# board.net
KiCad netlist of a schematic drawn in EAGLE
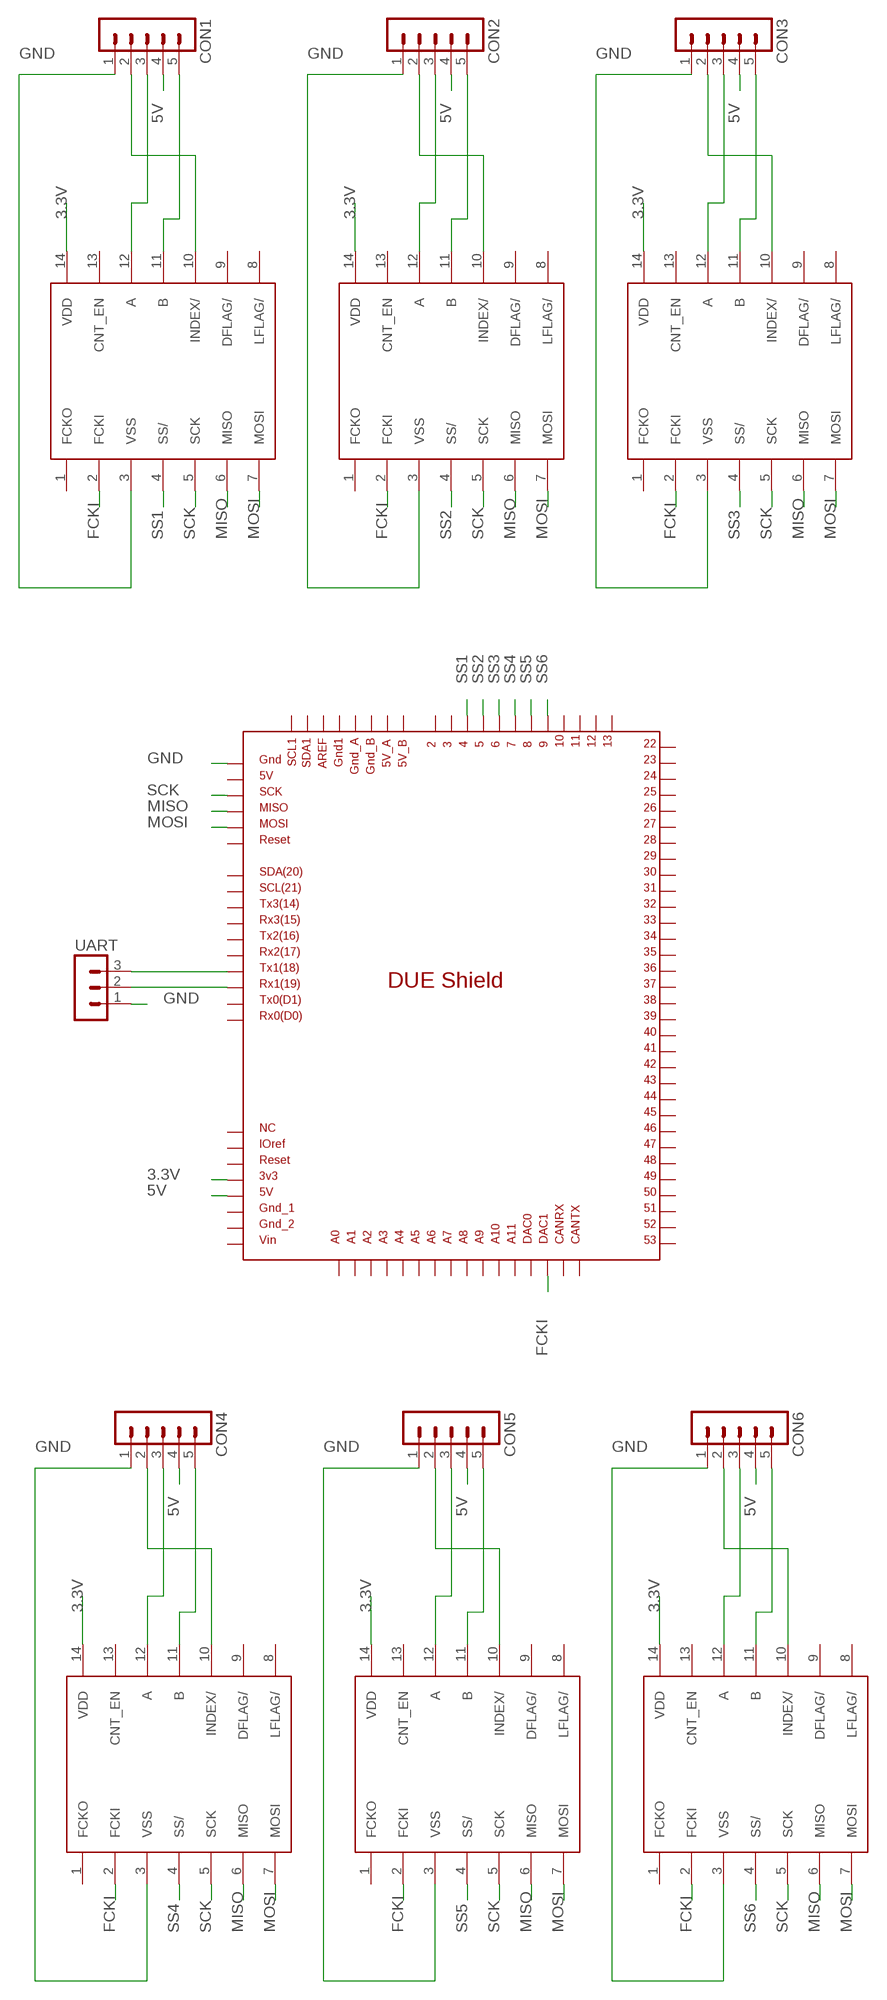
[diagram p0: schematic, sheet 1]

(export (version "E")
  (design (tool "Eeschema 10.0.6"))
  (components
    (comp (ref "CON1")
      (value "MA05-1")
      (footprint "eagle-import:MA05-1")
      (libsource (lib "eagle-import") (part "MA05-1"))
    )
    (comp (ref "CON2")
      (value "MA05-1")
      (footprint "eagle-import:MA05-1")
      (libsource (lib "eagle-import") (part "MA05-1"))
    )
    (comp (ref "CON3")
      (value "MA05-1")
      (footprint "eagle-import:MA05-1")
      (libsource (lib "eagle-import") (part "MA05-1"))
    )
    (comp (ref "CON4")
      (value "MA05-1(BOTTOM)")
      (footprint "eagle-import:MA05-1(BOTTOM)")
      (libsource (lib "eagle-import") (part "MA05-1(BOTTOM)"))
    )
    (comp (ref "CON5")
      (value "MA05-1(BOTTOM)")
      (footprint "eagle-import:MA05-1(BOTTOM)")
      (libsource (lib "eagle-import") (part "MA05-1(BOTTOM)"))
    )
    (comp (ref "CON6")
      (value "MA05-1(BOTTOM)")
      (footprint "eagle-import:MA05-1(BOTTOM)")
      (libsource (lib "eagle-import") (part "MA05-1(BOTTOM)"))
    )
    (comp (ref "IC1")
      (value "LFLS7366R")
      (footprint "eagle-import:SO14")
      (libsource (lib "eagle-import") (part "LFLS7366R"))
    )
    (comp (ref "IC2")
      (value "LFLS7366R")
      (footprint "eagle-import:SO14")
      (libsource (lib "eagle-import") (part "LFLS7366R"))
    )
    (comp (ref "IC3")
      (value "LFLS7366R")
      (footprint "eagle-import:SO14")
      (libsource (lib "eagle-import") (part "LFLS7366R"))
    )
    (comp (ref "IC4")
      (value "LFLS7366R")
      (footprint "eagle-import:SO14")
      (libsource (lib "eagle-import") (part "LFLS7366R"))
    )
    (comp (ref "IC5")
      (value "LFLS7366R")
      (footprint "eagle-import:SO14")
      (libsource (lib "eagle-import") (part "LFLS7366R"))
    )
    (comp (ref "IC6")
      (value "LFLS7366R")
      (footprint "eagle-import:SO14")
      (libsource (lib "eagle-import") (part "LFLS7366R"))
    )
    (comp (ref "U$1")
      (value "DUE(ENCODER)")
      (footprint "eagle-import:DUE(ENCODER)")
      (libsource (lib "eagle-import") (part "DUE(ENCODER)"))
    )
    (comp (ref "UART")
      (value "MA03-1")
      (footprint "eagle-import:MA03-1")
      (libsource (lib "eagle-import") (part "MA03-1"))
    )
  )
  (nets
    (net (code "1") (name "/3.3V") (class "Default")
      (node (ref "IC1") (pin "14") (pinfunction "VDD_14") (pintype "bidirectional"))
      (node (ref "IC2") (pin "14") (pinfunction "VDD_14") (pintype "bidirectional"))
      (node (ref "IC3") (pin "14") (pinfunction "VDD_14") (pintype "bidirectional"))
      (node (ref "IC4") (pin "14") (pinfunction "VDD_14") (pintype "bidirectional"))
      (node (ref "IC5") (pin "14") (pinfunction "VDD_14") (pintype "bidirectional"))
      (node (ref "IC6") (pin "14") (pinfunction "VDD_14") (pintype "bidirectional"))
      (node (ref "U$1") (pin "3V3") (pinfunction "3V3_3V3") (pintype "bidirectional"))
    )
    (net (code "2") (name "/5V") (class "Default")
      (node (ref "CON1") (pin "4") (pinfunction "4_4") (pintype "passive"))
      (node (ref "CON2") (pin "4") (pinfunction "4_4") (pintype "passive"))
      (node (ref "CON3") (pin "4") (pinfunction "4_4") (pintype "passive"))
      (node (ref "CON4") (pin "4") (pinfunction "4_4") (pintype "passive"))
      (node (ref "CON5") (pin "4") (pinfunction "4_4") (pintype "passive"))
      (node (ref "CON6") (pin "4") (pinfunction "4_4") (pintype "passive"))
      (node (ref "U$1") (pin "5V") (pinfunction "5V_5V") (pintype "bidirectional"))
    )
    (net (code "3") (name "/FCKI") (class "Default")
      (node (ref "IC1") (pin "2") (pinfunction "FCKI_2") (pintype "bidirectional"))
      (node (ref "IC2") (pin "2") (pinfunction "FCKI_2") (pintype "bidirectional"))
      (node (ref "IC3") (pin "2") (pinfunction "FCKI_2") (pintype "bidirectional"))
      (node (ref "IC4") (pin "2") (pinfunction "FCKI_2") (pintype "bidirectional"))
      (node (ref "IC5") (pin "2") (pinfunction "FCKI_2") (pintype "bidirectional"))
      (node (ref "IC6") (pin "2") (pinfunction "FCKI_2") (pintype "bidirectional"))
      (node (ref "U$1") (pin "DAC1") (pinfunction "DAC1_DAC1") (pintype "bidirectional"))
    )
    (net (code "4") (name "/GND") (class "Default")
      (node (ref "CON1") (pin "1") (pinfunction "1_1") (pintype "passive"))
      (node (ref "CON2") (pin "1") (pinfunction "1_1") (pintype "passive"))
      (node (ref "CON3") (pin "1") (pinfunction "1_1") (pintype "passive"))
      (node (ref "CON4") (pin "1") (pinfunction "1_1") (pintype "passive"))
      (node (ref "CON5") (pin "1") (pinfunction "1_1") (pintype "passive"))
      (node (ref "CON6") (pin "1") (pinfunction "1_1") (pintype "passive"))
      (node (ref "IC1") (pin "3") (pinfunction "VSS_3") (pintype "bidirectional"))
      (node (ref "IC2") (pin "3") (pinfunction "VSS_3") (pintype "bidirectional"))
      (node (ref "IC3") (pin "3") (pinfunction "VSS_3") (pintype "bidirectional"))
      (node (ref "IC4") (pin "3") (pinfunction "VSS_3") (pintype "bidirectional"))
      (node (ref "IC5") (pin "3") (pinfunction "VSS_3") (pintype "bidirectional"))
      (node (ref "IC6") (pin "3") (pinfunction "VSS_3") (pintype "bidirectional"))
      (node (ref "U$1") (pin "5V_ICSP") (pinfunction "5V_ICSP_5V_ICSP") (pintype "bidirectional"))
      (node (ref "UART") (pin "1") (pinfunction "1_1") (pintype "passive"))
    )
    (net (code "5") (name "/MISO") (class "Default")
      (node (ref "IC1") (pin "6") (pinfunction "MISO_6") (pintype "bidirectional"))
      (node (ref "IC2") (pin "6") (pinfunction "MISO_6") (pintype "bidirectional"))
      (node (ref "IC3") (pin "6") (pinfunction "MISO_6") (pintype "bidirectional"))
      (node (ref "IC4") (pin "6") (pinfunction "MISO_6") (pintype "bidirectional"))
      (node (ref "IC5") (pin "6") (pinfunction "MISO_6") (pintype "bidirectional"))
      (node (ref "IC6") (pin "6") (pinfunction "MISO_6") (pintype "bidirectional"))
      (node (ref "U$1") (pin "MISO_ICSP") (pinfunction "MISO_ICSP_MISO_ICSP") (pintype "bidirectional"))
    )
    (net (code "6") (name "/MOSI") (class "Default")
      (node (ref "IC1") (pin "7") (pinfunction "MOSI_7") (pintype "bidirectional"))
      (node (ref "IC2") (pin "7") (pinfunction "MOSI_7") (pintype "bidirectional"))
      (node (ref "IC3") (pin "7") (pinfunction "MOSI_7") (pintype "bidirectional"))
      (node (ref "IC4") (pin "7") (pinfunction "MOSI_7") (pintype "bidirectional"))
      (node (ref "IC5") (pin "7") (pinfunction "MOSI_7") (pintype "bidirectional"))
      (node (ref "IC6") (pin "7") (pinfunction "MOSI_7") (pintype "bidirectional"))
      (node (ref "U$1") (pin "MOSI_ICSP") (pinfunction "MOSI_ICSP_MOSI_ICSP") (pintype "bidirectional"))
    )
    (net (code "7") (name "/SCK") (class "Default")
      (node (ref "IC1") (pin "5") (pinfunction "SCK_5") (pintype "bidirectional"))
      (node (ref "IC2") (pin "5") (pinfunction "SCK_5") (pintype "bidirectional"))
      (node (ref "IC3") (pin "5") (pinfunction "SCK_5") (pintype "bidirectional"))
      (node (ref "IC4") (pin "5") (pinfunction "SCK_5") (pintype "bidirectional"))
      (node (ref "IC5") (pin "5") (pinfunction "SCK_5") (pintype "bidirectional"))
      (node (ref "IC6") (pin "5") (pinfunction "SCK_5") (pintype "bidirectional"))
      (node (ref "U$1") (pin "SCK_ICSP") (pinfunction "SCK_ICSP_SCK_ICSP") (pintype "bidirectional"))
    )
    (net (code "8") (name "/SS1") (class "Default")
      (node (ref "IC1") (pin "4") (pinfunction "SS/_4") (pintype "bidirectional"))
      (node (ref "U$1") (pin "4") (pinfunction "4_4") (pintype "bidirectional"))
    )
    (net (code "9") (name "/SS2") (class "Default")
      (node (ref "IC2") (pin "4") (pinfunction "SS/_4") (pintype "bidirectional"))
      (node (ref "U$1") (pin "5") (pinfunction "5_5") (pintype "bidirectional"))
    )
    (net (code "10") (name "/SS3") (class "Default")
      (node (ref "IC3") (pin "4") (pinfunction "SS/_4") (pintype "bidirectional"))
      (node (ref "U$1") (pin "6") (pinfunction "6_6") (pintype "bidirectional"))
    )
    (net (code "11") (name "/SS4") (class "Default")
      (node (ref "IC4") (pin "4") (pinfunction "SS/_4") (pintype "bidirectional"))
      (node (ref "U$1") (pin "7") (pinfunction "7_7") (pintype "bidirectional"))
    )
    (net (code "12") (name "/SS5") (class "Default")
      (node (ref "IC5") (pin "4") (pinfunction "SS/_4") (pintype "bidirectional"))
      (node (ref "U$1") (pin "8") (pinfunction "8_8") (pintype "bidirectional"))
    )
    (net (code "13") (name "/SS6") (class "Default")
      (node (ref "IC6") (pin "4") (pinfunction "SS/_4") (pintype "bidirectional"))
      (node (ref "U$1") (pin "9") (pinfunction "9_9") (pintype "bidirectional"))
    )
    (net (code "14") (name "Net-(IC1-A)") (class "Default")
      (node (ref "CON1") (pin "3") (pinfunction "3_3") (pintype "passive"))
      (node (ref "IC1") (pin "12") (pinfunction "A_12") (pintype "bidirectional"))
    )
    (net (code "15") (name "Net-(IC1-B)") (class "Default")
      (node (ref "CON1") (pin "5") (pinfunction "5_5") (pintype "passive"))
      (node (ref "IC1") (pin "11") (pinfunction "B_11") (pintype "bidirectional"))
    )
    (net (code "16") (name "Net-(IC1-INDEX{slash})") (class "Default")
      (node (ref "CON1") (pin "2") (pinfunction "2_2") (pintype "passive"))
      (node (ref "IC1") (pin "10") (pinfunction "INDEX/_10") (pintype "bidirectional"))
    )
    (net (code "17") (name "Net-(IC2-A)") (class "Default")
      (node (ref "CON2") (pin "3") (pinfunction "3_3") (pintype "passive"))
      (node (ref "IC2") (pin "12") (pinfunction "A_12") (pintype "bidirectional"))
    )
    (net (code "18") (name "Net-(IC2-B)") (class "Default")
      (node (ref "CON2") (pin "5") (pinfunction "5_5") (pintype "passive"))
      (node (ref "IC2") (pin "11") (pinfunction "B_11") (pintype "bidirectional"))
    )
    (net (code "19") (name "Net-(IC2-INDEX{slash})") (class "Default")
      (node (ref "CON2") (pin "2") (pinfunction "2_2") (pintype "passive"))
      (node (ref "IC2") (pin "10") (pinfunction "INDEX/_10") (pintype "bidirectional"))
    )
    (net (code "20") (name "Net-(IC3-A)") (class "Default")
      (node (ref "CON3") (pin "3") (pinfunction "3_3") (pintype "passive"))
      (node (ref "IC3") (pin "12") (pinfunction "A_12") (pintype "bidirectional"))
    )
    (net (code "21") (name "Net-(IC3-B)") (class "Default")
      (node (ref "CON3") (pin "5") (pinfunction "5_5") (pintype "passive"))
      (node (ref "IC3") (pin "11") (pinfunction "B_11") (pintype "bidirectional"))
    )
    (net (code "22") (name "Net-(IC3-INDEX{slash})") (class "Default")
      (node (ref "CON3") (pin "2") (pinfunction "2_2") (pintype "passive"))
      (node (ref "IC3") (pin "10") (pinfunction "INDEX/_10") (pintype "bidirectional"))
    )
    (net (code "23") (name "Net-(IC4-A)") (class "Default")
      (node (ref "CON4") (pin "3") (pinfunction "3_3") (pintype "passive"))
      (node (ref "IC4") (pin "12") (pinfunction "A_12") (pintype "bidirectional"))
    )
    (net (code "24") (name "Net-(IC4-B)") (class "Default")
      (node (ref "CON4") (pin "5") (pinfunction "5_5") (pintype "passive"))
      (node (ref "IC4") (pin "11") (pinfunction "B_11") (pintype "bidirectional"))
    )
    (net (code "25") (name "Net-(IC4-INDEX{slash})") (class "Default")
      (node (ref "CON4") (pin "2") (pinfunction "2_2") (pintype "passive"))
      (node (ref "IC4") (pin "10") (pinfunction "INDEX/_10") (pintype "bidirectional"))
    )
    (net (code "26") (name "Net-(IC5-A)") (class "Default")
      (node (ref "CON5") (pin "3") (pinfunction "3_3") (pintype "passive"))
      (node (ref "IC5") (pin "12") (pinfunction "A_12") (pintype "bidirectional"))
    )
    (net (code "27") (name "Net-(IC5-B)") (class "Default")
      (node (ref "CON5") (pin "5") (pinfunction "5_5") (pintype "passive"))
      (node (ref "IC5") (pin "11") (pinfunction "B_11") (pintype "bidirectional"))
    )
    (net (code "28") (name "Net-(IC5-INDEX{slash})") (class "Default")
      (node (ref "CON5") (pin "2") (pinfunction "2_2") (pintype "passive"))
      (node (ref "IC5") (pin "10") (pinfunction "INDEX/_10") (pintype "bidirectional"))
    )
    (net (code "29") (name "Net-(IC6-A)") (class "Default")
      (node (ref "CON6") (pin "3") (pinfunction "3_3") (pintype "passive"))
      (node (ref "IC6") (pin "12") (pinfunction "A_12") (pintype "bidirectional"))
    )
    (net (code "30") (name "Net-(IC6-B)") (class "Default")
      (node (ref "CON6") (pin "5") (pinfunction "5_5") (pintype "passive"))
      (node (ref "IC6") (pin "11") (pinfunction "B_11") (pintype "bidirectional"))
    )
    (net (code "31") (name "Net-(IC6-INDEX{slash})") (class "Default")
      (node (ref "CON6") (pin "2") (pinfunction "2_2") (pintype "passive"))
      (node (ref "IC6") (pin "10") (pinfunction "INDEX/_10") (pintype "bidirectional"))
    )
    (net (code "32") (name "Net-(U$1-PadRX1)") (class "Default")
      (node (ref "U$1") (pin "RX1") (pinfunction "RX1_RX1") (pintype "bidirectional"))
      (node (ref "UART") (pin "2") (pinfunction "2_2") (pintype "passive"))
    )
    (net (code "33") (name "Net-(U$1-PadTX1)") (class "Default")
      (node (ref "U$1") (pin "TX1") (pinfunction "TX1_TX1") (pintype "bidirectional"))
      (node (ref "UART") (pin "3") (pinfunction "3_3") (pintype "passive"))
    )
    (net (code "34") (name "unconnected-(IC1-CNT_EN-Pad13)") (class "Default")
      (node (ref "IC1") (pin "13") (pinfunction "CNT_EN_13") (pintype "bidirectional"))
    )
    (net (code "35") (name "unconnected-(IC1-DFLAG{slash}-Pad9)") (class "Default")
      (node (ref "IC1") (pin "9") (pinfunction "DFLAG/_9") (pintype "bidirectional"))
    )
    (net (code "36") (name "unconnected-(IC1-FCKO-Pad1)") (class "Default")
      (node (ref "IC1") (pin "1") (pinfunction "FCKO_1") (pintype "bidirectional"))
    )
    (net (code "37") (name "unconnected-(IC1-LFLAG{slash}-Pad8)") (class "Default")
      (node (ref "IC1") (pin "8") (pinfunction "LFLAG/_8") (pintype "bidirectional"))
    )
    (net (code "38") (name "unconnected-(IC2-CNT_EN-Pad13)") (class "Default")
      (node (ref "IC2") (pin "13") (pinfunction "CNT_EN_13") (pintype "bidirectional"))
    )
    (net (code "39") (name "unconnected-(IC2-DFLAG{slash}-Pad9)") (class "Default")
      (node (ref "IC2") (pin "9") (pinfunction "DFLAG/_9") (pintype "bidirectional"))
    )
    (net (code "40") (name "unconnected-(IC2-FCKO-Pad1)") (class "Default")
      (node (ref "IC2") (pin "1") (pinfunction "FCKO_1") (pintype "bidirectional"))
    )
    (net (code "41") (name "unconnected-(IC2-LFLAG{slash}-Pad8)") (class "Default")
      (node (ref "IC2") (pin "8") (pinfunction "LFLAG/_8") (pintype "bidirectional"))
    )
    (net (code "42") (name "unconnected-(IC3-CNT_EN-Pad13)") (class "Default")
      (node (ref "IC3") (pin "13") (pinfunction "CNT_EN_13") (pintype "bidirectional"))
    )
    (net (code "43") (name "unconnected-(IC3-DFLAG{slash}-Pad9)") (class "Default")
      (node (ref "IC3") (pin "9") (pinfunction "DFLAG/_9") (pintype "bidirectional"))
    )
    (net (code "44") (name "unconnected-(IC3-FCKO-Pad1)") (class "Default")
      (node (ref "IC3") (pin "1") (pinfunction "FCKO_1") (pintype "bidirectional"))
    )
    (net (code "45") (name "unconnected-(IC3-LFLAG{slash}-Pad8)") (class "Default")
      (node (ref "IC3") (pin "8") (pinfunction "LFLAG/_8") (pintype "bidirectional"))
    )
    (net (code "46") (name "unconnected-(IC4-CNT_EN-Pad13)") (class "Default")
      (node (ref "IC4") (pin "13") (pinfunction "CNT_EN_13") (pintype "bidirectional"))
    )
    (net (code "47") (name "unconnected-(IC4-DFLAG{slash}-Pad9)") (class "Default")
      (node (ref "IC4") (pin "9") (pinfunction "DFLAG/_9") (pintype "bidirectional"))
    )
    (net (code "48") (name "unconnected-(IC4-FCKO-Pad1)") (class "Default")
      (node (ref "IC4") (pin "1") (pinfunction "FCKO_1") (pintype "bidirectional"))
    )
    (net (code "49") (name "unconnected-(IC4-LFLAG{slash}-Pad8)") (class "Default")
      (node (ref "IC4") (pin "8") (pinfunction "LFLAG/_8") (pintype "bidirectional"))
    )
    (net (code "50") (name "unconnected-(IC5-CNT_EN-Pad13)") (class "Default")
      (node (ref "IC5") (pin "13") (pinfunction "CNT_EN_13") (pintype "bidirectional"))
    )
    (net (code "51") (name "unconnected-(IC5-DFLAG{slash}-Pad9)") (class "Default")
      (node (ref "IC5") (pin "9") (pinfunction "DFLAG/_9") (pintype "bidirectional"))
    )
    (net (code "52") (name "unconnected-(IC5-FCKO-Pad1)") (class "Default")
      (node (ref "IC5") (pin "1") (pinfunction "FCKO_1") (pintype "bidirectional"))
    )
    (net (code "53") (name "unconnected-(IC5-LFLAG{slash}-Pad8)") (class "Default")
      (node (ref "IC5") (pin "8") (pinfunction "LFLAG/_8") (pintype "bidirectional"))
    )
    (net (code "54") (name "unconnected-(IC6-CNT_EN-Pad13)") (class "Default")
      (node (ref "IC6") (pin "13") (pinfunction "CNT_EN_13") (pintype "bidirectional"))
    )
    (net (code "55") (name "unconnected-(IC6-DFLAG{slash}-Pad9)") (class "Default")
      (node (ref "IC6") (pin "9") (pinfunction "DFLAG/_9") (pintype "bidirectional"))
    )
    (net (code "56") (name "unconnected-(IC6-FCKO-Pad1)") (class "Default")
      (node (ref "IC6") (pin "1") (pinfunction "FCKO_1") (pintype "bidirectional"))
    )
    (net (code "57") (name "unconnected-(IC6-LFLAG{slash}-Pad8)") (class "Default")
      (node (ref "IC6") (pin "8") (pinfunction "LFLAG/_8") (pintype "bidirectional"))
    )
    (net (code "58") (name "unconnected-(U$1-Pad2)") (class "Default")
      (node (ref "U$1") (pin "2") (pinfunction "2_2") (pintype "bidirectional"))
    )
    (net (code "59") (name "unconnected-(U$1-Pad3)") (class "Default")
      (node (ref "U$1") (pin "3") (pinfunction "3_3") (pintype "bidirectional"))
    )
    (net (code "60") (name "unconnected-(U$1-Pad5V_A)") (class "Default")
      (node (ref "U$1") (pin "5V_A") (pinfunction "5V_A_5V_A") (pintype "bidirectional"))
    )
    (net (code "61") (name "unconnected-(U$1-Pad5V_B)") (class "Default")
      (node (ref "U$1") (pin "5V_B") (pinfunction "5V_B_5V_B") (pintype "bidirectional"))
    )
    (net (code "62") (name "unconnected-(U$1-Pad10)") (class "Default")
      (node (ref "U$1") (pin "10") (pinfunction "10_10") (pintype "bidirectional"))
    )
    (net (code "63") (name "unconnected-(U$1-Pad11)") (class "Default")
      (node (ref "U$1") (pin "11") (pinfunction "11_11") (pintype "bidirectional"))
    )
    (net (code "64") (name "unconnected-(U$1-Pad12)") (class "Default")
      (node (ref "U$1") (pin "12") (pinfunction "12_12") (pintype "bidirectional"))
    )
    (net (code "65") (name "unconnected-(U$1-Pad13)") (class "Default")
      (node (ref "U$1") (pin "13") (pinfunction "13_13") (pintype "bidirectional"))
    )
    (net (code "66") (name "unconnected-(U$1-Pad22)") (class "Default")
      (node (ref "U$1") (pin "22") (pinfunction "22_22") (pintype "bidirectional"))
    )
    (net (code "67") (name "unconnected-(U$1-Pad23)") (class "Default")
      (node (ref "U$1") (pin "23") (pinfunction "23_23") (pintype "bidirectional"))
    )
    (net (code "68") (name "unconnected-(U$1-Pad24)") (class "Default")
      (node (ref "U$1") (pin "24") (pinfunction "24_24") (pintype "bidirectional"))
    )
    (net (code "69") (name "unconnected-(U$1-Pad25)") (class "Default")
      (node (ref "U$1") (pin "25") (pinfunction "25_25") (pintype "bidirectional"))
    )
    (net (code "70") (name "unconnected-(U$1-Pad26)") (class "Default")
      (node (ref "U$1") (pin "26") (pinfunction "26_26") (pintype "bidirectional"))
    )
    (net (code "71") (name "unconnected-(U$1-Pad27)") (class "Default")
      (node (ref "U$1") (pin "27") (pinfunction "27_27") (pintype "bidirectional"))
    )
    (net (code "72") (name "unconnected-(U$1-Pad28)") (class "Default")
      (node (ref "U$1") (pin "28") (pinfunction "28_28") (pintype "bidirectional"))
    )
    (net (code "73") (name "unconnected-(U$1-Pad29)") (class "Default")
      (node (ref "U$1") (pin "29") (pinfunction "29_29") (pintype "bidirectional"))
    )
    (net (code "74") (name "unconnected-(U$1-Pad30)") (class "Default")
      (node (ref "U$1") (pin "30") (pinfunction "30_30") (pintype "bidirectional"))
    )
    (net (code "75") (name "unconnected-(U$1-Pad31)") (class "Default")
      (node (ref "U$1") (pin "31") (pinfunction "31_31") (pintype "bidirectional"))
    )
    (net (code "76") (name "unconnected-(U$1-Pad32)") (class "Default")
      (node (ref "U$1") (pin "32") (pinfunction "32_32") (pintype "bidirectional"))
    )
    (net (code "77") (name "unconnected-(U$1-Pad33)") (class "Default")
      (node (ref "U$1") (pin "33") (pinfunction "33_33") (pintype "bidirectional"))
    )
    (net (code "78") (name "unconnected-(U$1-Pad34)") (class "Default")
      (node (ref "U$1") (pin "34") (pinfunction "34_34") (pintype "bidirectional"))
    )
    (net (code "79") (name "unconnected-(U$1-Pad35)") (class "Default")
      (node (ref "U$1") (pin "35") (pinfunction "35_35") (pintype "bidirectional"))
    )
    (net (code "80") (name "unconnected-(U$1-Pad36)") (class "Default")
      (node (ref "U$1") (pin "36") (pinfunction "36_36") (pintype "bidirectional"))
    )
    (net (code "81") (name "unconnected-(U$1-Pad37)") (class "Default")
      (node (ref "U$1") (pin "37") (pinfunction "37_37") (pintype "bidirectional"))
    )
    (net (code "82") (name "unconnected-(U$1-Pad38)") (class "Default")
      (node (ref "U$1") (pin "38") (pinfunction "38_38") (pintype "bidirectional"))
    )
    (net (code "83") (name "unconnected-(U$1-Pad39)") (class "Default")
      (node (ref "U$1") (pin "39") (pinfunction "39_39") (pintype "bidirectional"))
    )
    (net (code "84") (name "unconnected-(U$1-Pad40)") (class "Default")
      (node (ref "U$1") (pin "40") (pinfunction "40_40") (pintype "bidirectional"))
    )
    (net (code "85") (name "unconnected-(U$1-Pad41)") (class "Default")
      (node (ref "U$1") (pin "41") (pinfunction "41_41") (pintype "bidirectional"))
    )
    (net (code "86") (name "unconnected-(U$1-Pad42)") (class "Default")
      (node (ref "U$1") (pin "42") (pinfunction "42_42") (pintype "bidirectional"))
    )
    (net (code "87") (name "unconnected-(U$1-Pad43)") (class "Default")
      (node (ref "U$1") (pin "43") (pinfunction "43_43") (pintype "bidirectional"))
    )
    (net (code "88") (name "unconnected-(U$1-Pad44)") (class "Default")
      (node (ref "U$1") (pin "44") (pinfunction "44_44") (pintype "bidirectional"))
    )
    (net (code "89") (name "unconnected-(U$1-Pad45)") (class "Default")
      (node (ref "U$1") (pin "45") (pinfunction "45_45") (pintype "bidirectional"))
    )
    (net (code "90") (name "unconnected-(U$1-Pad46)") (class "Default")
      (node (ref "U$1") (pin "46") (pinfunction "46_46") (pintype "bidirectional"))
    )
    (net (code "91") (name "unconnected-(U$1-Pad47)") (class "Default")
      (node (ref "U$1") (pin "47") (pinfunction "47_47") (pintype "bidirectional"))
    )
    (net (code "92") (name "unconnected-(U$1-Pad48)") (class "Default")
      (node (ref "U$1") (pin "48") (pinfunction "48_48") (pintype "bidirectional"))
    )
    (net (code "93") (name "unconnected-(U$1-Pad49)") (class "Default")
      (node (ref "U$1") (pin "49") (pinfunction "49_49") (pintype "bidirectional"))
    )
    (net (code "94") (name "unconnected-(U$1-Pad50)") (class "Default")
      (node (ref "U$1") (pin "50") (pinfunction "50_50") (pintype "bidirectional"))
    )
    (net (code "95") (name "unconnected-(U$1-Pad51)") (class "Default")
      (node (ref "U$1") (pin "51") (pinfunction "51_51") (pintype "bidirectional"))
    )
    (net (code "96") (name "unconnected-(U$1-Pad52)") (class "Default")
      (node (ref "U$1") (pin "52") (pinfunction "52_52") (pintype "bidirectional"))
    )
    (net (code "97") (name "unconnected-(U$1-Pad53)") (class "Default")
      (node (ref "U$1") (pin "53") (pinfunction "53_53") (pintype "bidirectional"))
    )
    (net (code "98") (name "unconnected-(U$1-PadA0)") (class "Default")
      (node (ref "U$1") (pin "A0") (pinfunction "A0_A0") (pintype "bidirectional"))
    )
    (net (code "99") (name "unconnected-(U$1-PadA1)") (class "Default")
      (node (ref "U$1") (pin "A1") (pinfunction "A1_A1") (pintype "bidirectional"))
    )
    (net (code "100") (name "unconnected-(U$1-PadA2)") (class "Default")
      (node (ref "U$1") (pin "A2") (pinfunction "A2_A2") (pintype "bidirectional"))
    )
    (net (code "101") (name "unconnected-(U$1-PadA3)") (class "Default")
      (node (ref "U$1") (pin "A3") (pinfunction "A3_A3") (pintype "bidirectional"))
    )
    (net (code "102") (name "unconnected-(U$1-PadA4)") (class "Default")
      (node (ref "U$1") (pin "A4") (pinfunction "A4_A4") (pintype "bidirectional"))
    )
    (net (code "103") (name "unconnected-(U$1-PadA5)") (class "Default")
      (node (ref "U$1") (pin "A5") (pinfunction "A5_A5") (pintype "bidirectional"))
    )
    (net (code "104") (name "unconnected-(U$1-PadA6)") (class "Default")
      (node (ref "U$1") (pin "A6") (pinfunction "A6_A6") (pintype "bidirectional"))
    )
    (net (code "105") (name "unconnected-(U$1-PadA7)") (class "Default")
      (node (ref "U$1") (pin "A7") (pinfunction "A7_A7") (pintype "bidirectional"))
    )
    (net (code "106") (name "unconnected-(U$1-PadA8)") (class "Default")
      (node (ref "U$1") (pin "A8") (pinfunction "A8_A8") (pintype "bidirectional"))
    )
    (net (code "107") (name "unconnected-(U$1-PadA9)") (class "Default")
      (node (ref "U$1") (pin "A9") (pinfunction "A9_A9") (pintype "bidirectional"))
    )
    (net (code "108") (name "unconnected-(U$1-PadA10)") (class "Default")
      (node (ref "U$1") (pin "A10") (pinfunction "A10_A10") (pintype "bidirectional"))
    )
    (net (code "109") (name "unconnected-(U$1-PadA11)") (class "Default")
      (node (ref "U$1") (pin "A11") (pinfunction "A11_A11") (pintype "bidirectional"))
    )
    (net (code "110") (name "unconnected-(U$1-PadAREF)") (class "Default")
      (node (ref "U$1") (pin "AREF") (pinfunction "AREF_AREF") (pintype "bidirectional"))
    )
    (net (code "111") (name "unconnected-(U$1-PadCANRX)") (class "Default")
      (node (ref "U$1") (pin "CANRX") (pinfunction "CANRX_CANRX") (pintype "bidirectional"))
    )
    (net (code "112") (name "unconnected-(U$1-PadCANTX)") (class "Default")
      (node (ref "U$1") (pin "CANTX") (pinfunction "CANTX_CANTX") (pintype "bidirectional"))
    )
    (net (code "113") (name "unconnected-(U$1-PadDAC0)") (class "Default")
      (node (ref "U$1") (pin "DAC0") (pinfunction "DAC0_DAC0") (pintype "bidirectional"))
    )
    (net (code "114") (name "unconnected-(U$1-PadGND1)") (class "Default")
      (node (ref "U$1") (pin "GND1") (pinfunction "GND1_GND1") (pintype "bidirectional"))
    )
    (net (code "115") (name "unconnected-(U$1-PadGND_1)") (class "Default")
      (node (ref "U$1") (pin "GND_1") (pinfunction "GND_1_GND_1") (pintype "bidirectional"))
    )
    (net (code "116") (name "unconnected-(U$1-PadGND_2)") (class "Default")
      (node (ref "U$1") (pin "GND_2") (pinfunction "GND_2_GND_2") (pintype "bidirectional"))
    )
    (net (code "117") (name "unconnected-(U$1-PadGND_A)") (class "Default")
      (node (ref "U$1") (pin "GND_A") (pinfunction "GND_A_GND_A") (pintype "bidirectional"))
    )
    (net (code "118") (name "unconnected-(U$1-PadGND_B)") (class "Default")
      (node (ref "U$1") (pin "GND_B") (pinfunction "GND_B_GND_B") (pintype "bidirectional"))
    )
    (net (code "119") (name "unconnected-(U$1-PadGND_ICSP)") (class "Default")
      (node (ref "U$1") (pin "GND_ICSP") (pinfunction "GND_ICSP_GND_ICSP") (pintype "bidirectional"))
    )
    (net (code "120") (name "unconnected-(U$1-PadIOREF)") (class "Default")
      (node (ref "U$1") (pin "IOREF") (pinfunction "IOREF_IOREF") (pintype "bidirectional"))
    )
    (net (code "121") (name "unconnected-(U$1-PadNC)") (class "Default")
      (node (ref "U$1") (pin "NC") (pinfunction "NC_NC") (pintype "bidirectional"))
    )
    (net (code "122") (name "unconnected-(U$1-PadRESET)") (class "Default")
      (node (ref "U$1") (pin "RESET") (pinfunction "RESET_RESET") (pintype "bidirectional"))
    )
    (net (code "123") (name "unconnected-(U$1-PadRESET_ICSP)") (class "Default")
      (node (ref "U$1") (pin "RESET_ICSP") (pinfunction "RESET_ICSP_RESET_ICSP") (pintype "bidirectional"))
    )
    (net (code "124") (name "unconnected-(U$1-PadRX0)") (class "Default")
      (node (ref "U$1") (pin "RX0") (pinfunction "RX0_RX0") (pintype "bidirectional"))
    )
    (net (code "125") (name "unconnected-(U$1-PadRX2)") (class "Default")
      (node (ref "U$1") (pin "RX2") (pinfunction "RX2_RX2") (pintype "bidirectional"))
    )
    (net (code "126") (name "unconnected-(U$1-PadRX3)") (class "Default")
      (node (ref "U$1") (pin "RX3") (pinfunction "RX3_RX3") (pintype "bidirectional"))
    )
    (net (code "127") (name "unconnected-(U$1-PadSCL)") (class "Default")
      (node (ref "U$1") (pin "SCL") (pinfunction "SCL_SCL") (pintype "bidirectional"))
    )
    (net (code "128") (name "unconnected-(U$1-PadSCL1)") (class "Default")
      (node (ref "U$1") (pin "SCL1") (pinfunction "SCL1_SCL1") (pintype "bidirectional"))
    )
    (net (code "129") (name "unconnected-(U$1-PadSDA)") (class "Default")
      (node (ref "U$1") (pin "SDA") (pinfunction "SDA_SDA") (pintype "bidirectional"))
    )
    (net (code "130") (name "unconnected-(U$1-PadSDA1)") (class "Default")
      (node (ref "U$1") (pin "SDA1") (pinfunction "SDA1_SDA1") (pintype "bidirectional"))
    )
    (net (code "131") (name "unconnected-(U$1-PadTX0)") (class "Default")
      (node (ref "U$1") (pin "TX0") (pinfunction "TX0_TX0") (pintype "bidirectional"))
    )
    (net (code "132") (name "unconnected-(U$1-PadTX2)") (class "Default")
      (node (ref "U$1") (pin "TX2") (pinfunction "TX2_TX2") (pintype "bidirectional"))
    )
    (net (code "133") (name "unconnected-(U$1-PadTX3)") (class "Default")
      (node (ref "U$1") (pin "TX3") (pinfunction "TX3_TX3") (pintype "bidirectional"))
    )
    (net (code "134") (name "unconnected-(U$1-PadVIN)") (class "Default")
      (node (ref "U$1") (pin "VIN") (pinfunction "VIN_VIN") (pintype "bidirectional"))
    )
  )
)
